# Sheet1.net
KiCad netlist of a schematic drawn in Altium Designer
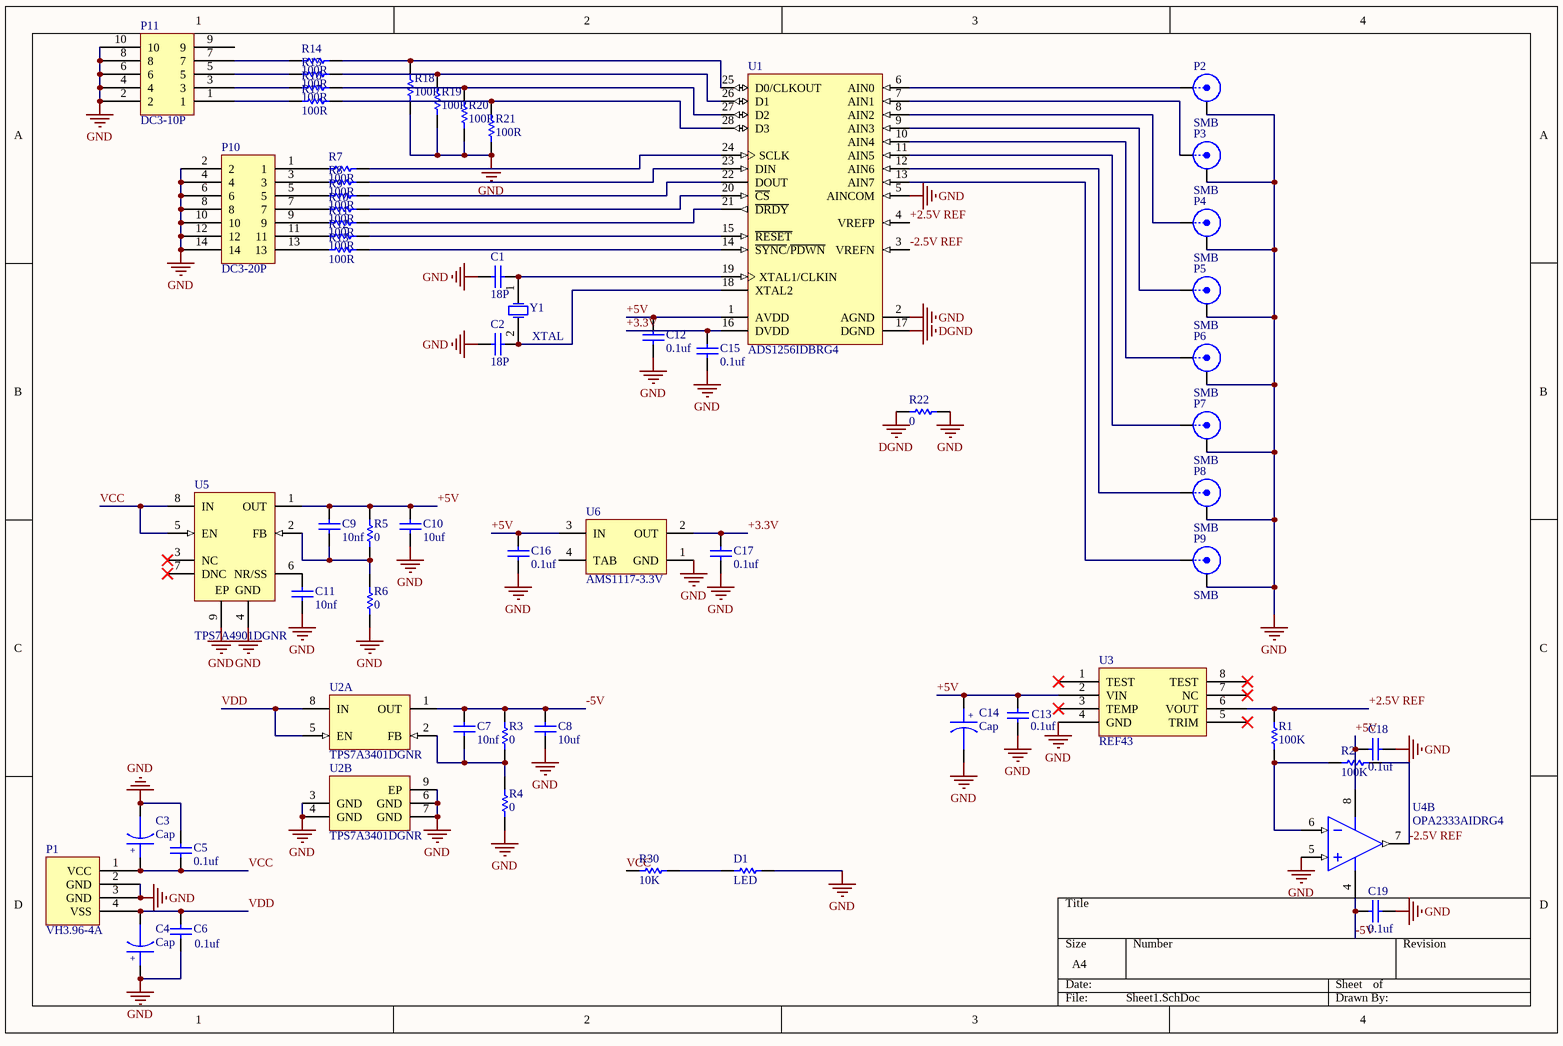
[diagram p0: Sheet1.SchDoc]

(export (version "E")
  (design (tool "Eeschema 10.0.6"))
  (components
    (comp (ref "C1") (value "18P") (footprint "0603C") (libsource (lib "Schlib1") (part "Cap")))
    (comp (ref "C2") (value "18P") (footprint "0603C") (libsource (lib "Schlib1") (part "Cap")))
    (comp (ref "C3")
      (value "Cap")
      (footprint "7343C-TYPE_D")
      (libsource (lib "Schlib1") (part "Tantalium Cap"))
    )
    (comp (ref "C4")
      (value "Cap")
      (footprint "7343C-TYPE_D")
      (libsource (lib "Schlib1") (part "Tantalium Cap"))
    )
    (comp (ref "C5") (value "0.1uf") (footprint "0805") (libsource (lib "Schlib1") (part "Cap")))
    (comp (ref "C6") (value "0.1uf") (footprint "0805") (libsource (lib "Schlib1") (part "Cap")))
    (comp (ref "C7") (value "10nf") (footprint "0805") (libsource (lib "Schlib1") (part "Cap")))
    (comp (ref "C8") (value "10uf") (footprint "0805") (libsource (lib "Schlib1") (part "Cap")))
    (comp (ref "C9") (value "10nf") (footprint "0805") (libsource (lib "Schlib1") (part "Cap")))
    (comp (ref "C10") (value "10uf") (footprint "0805") (libsource (lib "Schlib1") (part "Cap")))
    (comp (ref "C11") (value "10nf") (footprint "0805") (libsource (lib "Schlib1") (part "Cap")))
    (comp (ref "C12") (value "0.1uf") (footprint "0805") (libsource (lib "Schlib1") (part "Cap")))
    (comp (ref "C13") (value "0.1uf") (footprint "0805") (libsource (lib "Schlib1") (part "Cap")))
    (comp (ref "C14")
      (value "Cap")
      (footprint "3216C-TYPE_A")
      (libsource (lib "Schlib1") (part "Tantalium Cap"))
    )
    (comp (ref "C15") (value "0.1uf") (footprint "0805") (libsource (lib "Schlib1") (part "Cap")))
    (comp (ref "C16") (value "0.1uf") (footprint "0805") (libsource (lib "Schlib1") (part "Cap")))
    (comp (ref "C17") (value "0.1uf") (footprint "0805") (libsource (lib "Schlib1") (part "Cap")))
    (comp (ref "C18") (value "0.1uf") (footprint "3216C-TYPE_A") (libsource (lib "Schlib1") (part "Cap")))
    (comp (ref "C19") (value "0.1uf") (footprint "3216C-TYPE_A") (libsource (lib "Schlib1") (part "Cap")))
    (comp (ref "D1") (value "LED") (footprint "0805") (libsource (lib "Schlib1") (part "Res")))
    (comp (ref "P1")
      (value "VH3.96-4A")
      (footprint "VH3.96-4P")
      (libsource (lib "Schlib1") (part "VH3.96-4A"))
    )
    (comp (ref "P2")
      (value "SMB")
      (footprint "SMB_V-RJ45")
      (description "SMB Straight Connector")
      (fields (field (name "PUBLISHER") "Altium Limited"))
      (libsource (lib "Miscellaneous Connectors") (part "SMB"))
    )
    (comp (ref "P3")
      (value "SMB")
      (footprint "SMB_V-RJ45")
      (description "SMB Straight Connector")
      (fields (field (name "PUBLISHER") "Altium Limited"))
      (libsource (lib "Miscellaneous Connectors") (part "SMB"))
    )
    (comp (ref "P4")
      (value "SMB")
      (footprint "SMB_V-RJ45")
      (description "SMB Straight Connector")
      (fields (field (name "PUBLISHER") "Altium Limited"))
      (libsource (lib "Miscellaneous Connectors") (part "SMB"))
    )
    (comp (ref "P5")
      (value "SMB")
      (footprint "SMB_V-RJ45")
      (description "SMB Straight Connector")
      (fields (field (name "PUBLISHER") "Altium Limited"))
      (libsource (lib "Miscellaneous Connectors") (part "SMB"))
    )
    (comp (ref "P6")
      (value "SMB")
      (footprint "SMB_V-RJ45")
      (description "SMB Straight Connector")
      (fields (field (name "PUBLISHER") "Altium Limited"))
      (libsource (lib "Miscellaneous Connectors") (part "SMB"))
    )
    (comp (ref "P7")
      (value "SMB")
      (footprint "SMB_V-RJ45")
      (description "SMB Straight Connector")
      (fields (field (name "PUBLISHER") "Altium Limited"))
      (libsource (lib "Miscellaneous Connectors") (part "SMB"))
    )
    (comp (ref "P8")
      (value "SMB")
      (footprint "SMB_V-RJ45")
      (description "SMB Straight Connector")
      (fields (field (name "PUBLISHER") "Altium Limited"))
      (libsource (lib "Miscellaneous Connectors") (part "SMB"))
    )
    (comp (ref "P9")
      (value "SMB")
      (footprint "SMB_V-RJ45")
      (description "SMB Straight Connector")
      (fields (field (name "PUBLISHER") "Altium Limited"))
      (libsource (lib "Miscellaneous Connectors") (part "SMB"))
    )
    (comp (ref "P10") (value "DC3-20P") (footprint "DC3-14P") (libsource (lib "Schlib1") (part "DC3-20P")))
    (comp (ref "P11") (value "DC3-10P") (footprint "DC3-10P") (libsource (lib "Schlib1") (part "DC3-10P")))
    (comp (ref "R1") (value "100K") (footprint "0805") (libsource (lib "Schlib1") (part "Res")))
    (comp (ref "R2") (value "100K") (footprint "0805") (libsource (lib "Schlib1") (part "Res")))
    (comp (ref "R3") (value "0") (footprint "0805") (libsource (lib "Schlib1") (part "Res")))
    (comp (ref "R4") (value "0") (footprint "0805") (libsource (lib "Schlib1") (part "Res")))
    (comp (ref "R5") (value "0") (footprint "0805") (libsource (lib "Schlib1") (part "Res")))
    (comp (ref "R6") (value "0") (footprint "0805") (libsource (lib "Schlib1") (part "Res")))
    (comp (ref "R7") (value "100R") (footprint "0805") (libsource (lib "Schlib1") (part "Res")))
    (comp (ref "R8") (value "100R") (footprint "0805") (libsource (lib "Schlib1") (part "Res")))
    (comp (ref "R9") (value "100R") (footprint "0805") (libsource (lib "Schlib1") (part "Res")))
    (comp (ref "R10") (value "100R") (footprint "0805") (libsource (lib "Schlib1") (part "Res")))
    (comp (ref "R11") (value "100R") (footprint "0805") (libsource (lib "Schlib1") (part "Res")))
    (comp (ref "R12") (value "100R") (footprint "0805") (libsource (lib "Schlib1") (part "Res")))
    (comp (ref "R13") (value "100R") (footprint "0805") (libsource (lib "Schlib1") (part "Res")))
    (comp (ref "R14") (value "100R") (footprint "0805") (libsource (lib "Schlib1") (part "Res")))
    (comp (ref "R15") (value "100R") (footprint "0805") (libsource (lib "Schlib1") (part "Res")))
    (comp (ref "R16") (value "100R") (footprint "0805") (libsource (lib "Schlib1") (part "Res")))
    (comp (ref "R17") (value "100R") (footprint "0805") (libsource (lib "Schlib1") (part "Res")))
    (comp (ref "R18") (value "100R") (footprint "0805") (libsource (lib "Schlib1") (part "Res")))
    (comp (ref "R19") (value "100R") (footprint "0805") (libsource (lib "Schlib1") (part "Res")))
    (comp (ref "R20") (value "100R") (footprint "0805") (libsource (lib "Schlib1") (part "Res")))
    (comp (ref "R21") (value "100R") (footprint "0805") (libsource (lib "Schlib1") (part "Res")))
    (comp (ref "R22") (value "0") (footprint "0805") (libsource (lib "Schlib1") (part "Res")))
    (comp (ref "R30") (value "10K") (footprint "0805") (libsource (lib "Schlib1") (part "Res")))
    (comp (ref "U1")
      (value "ADS1256IDBRG4")
      (footprint "TI-DB28_N")
      (fields (field (name "MANUFACTURER") "Texas Instruments"))
      (libsource (lib "Schlib1") (part "ADS1256IDBRG4"))
    )
    (comp (ref "U2")
      (value "TPS7A3401DGNR")
      (footprint "TI-DGN8-1760X1425TP_N")
      (fields (field (name "MANUFACTURER") "Texas Instruments"))
      (libsource (lib "Schlib1") (part "TPS7A3401DGNR"))
    )
    (comp (ref "U3") (value "REF43") (footprint "TI-D8_M") (libsource (lib "Schlib1") (part "REF43")))
    (comp (ref "U4")
      (value "OPA2333AIDRG4")
      (footprint "TI-D8_N")
      (fields (field (name "MANUFACTURER") "Texas Instruments"))
      (libsource (lib "Schlib1") (part "OPA2333AIDRG4"))
    )
    (comp (ref "U5")
      (value "TPS7A4901DGNR")
      (footprint "TI-DGN8-1760X1425TP_N")
      (fields (field (name "MANUFACTURER") "Texas Instruments"))
      (libsource (lib "Schlib1") (part "TPS7A4901DGNR"))
    )
    (comp (ref "U6")
      (value "AMS1117-3.3V")
      (footprint "SOT-223")
      (libsource (lib "Schlib1") (part "AMS1117-3.3V"))
    )
    (comp (ref "Y1")
      (value "XTAL")
      (footprint "HC-49S")
      (description "Crystal Oscillator")
      (fields (field (name "PUBLISHER") "Altium Limited"))
      (libsource (lib "Miscellaneous Devices") (part "XTAL"))
    )
  )
  (nets
    (net (code "1") (name "/+2.5V REF") (class "Default")
      (node (ref "R1") (pin "2") (pinfunction "2_2") (pintype "passive"))
      (node (ref "U1") (pin "4") (pinfunction "VREFP_4") (pintype "input"))
      (node (ref "U3") (pin "6") (pinfunction "VOUT_6") (pintype "passive"))
    )
    (net (code "2") (name "/+3.3V") (class "Default")
      (node (ref "C15") (pin "2") (pinfunction "2_2") (pintype "passive"))
      (node (ref "C17") (pin "2") (pinfunction "2_2") (pintype "passive"))
      (node (ref "U1") (pin "16") (pinfunction "DVDD_16") (pintype "power_in"))
      (node (ref "U6") (pin "2") (pinfunction "OUT_2") (pintype "power_in"))
    )
    (net (code "3") (name "/+5V") (class "Default")
      (node (ref "C10") (pin "2") (pinfunction "2_2") (pintype "passive"))
      (node (ref "C12") (pin "2") (pinfunction "2_2") (pintype "passive"))
      (node (ref "C13") (pin "2") (pinfunction "2_2") (pintype "passive"))
      (node (ref "C14") (pin "1") (pinfunction "1_1") (pintype "passive"))
      (node (ref "C16") (pin "2") (pinfunction "2_2") (pintype "passive"))
      (node (ref "C18") (pin "1") (pinfunction "1_1") (pintype "passive"))
      (node (ref "C9") (pin "2") (pinfunction "2_2") (pintype "passive"))
      (node (ref "R5") (pin "2") (pinfunction "2_2") (pintype "passive"))
      (node (ref "U1") (pin "1") (pinfunction "AVDD_1") (pintype "power_in"))
      (node (ref "U3") (pin "2") (pinfunction "VIN_2") (pintype "passive"))
      (node (ref "U4") (pin "8") (pinfunction "V+_8") (pintype "power_in"))
      (node (ref "U5") (pin "1") (pinfunction "OUT_1") (pintype "power_in"))
      (node (ref "U6") (pin "3") (pinfunction "IN_3") (pintype "power_in"))
    )
    (net (code "4") (name "/-2.5V REF") (class "Default")
      (node (ref "R2") (pin "1") (pinfunction "1_1") (pintype "passive"))
      (node (ref "U1") (pin "3") (pinfunction "VREFN_3") (pintype "input"))
      (node (ref "U4") (pin "7") (pinfunction "OUT_B_7") (pintype "output"))
    )
    (net (code "5") (name "/-5V") (class "Default")
      (node (ref "C19") (pin "1") (pinfunction "1_1") (pintype "passive"))
      (node (ref "C7") (pin "2") (pinfunction "2_2") (pintype "passive"))
      (node (ref "C8") (pin "2") (pinfunction "2_2") (pintype "passive"))
      (node (ref "R3") (pin "2") (pinfunction "2_2") (pintype "passive"))
      (node (ref "U2") (pin "1") (pinfunction "OUT_1") (pintype "power_in"))
      (node (ref "U4") (pin "4") (pinfunction "V-_4") (pintype "power_in"))
    )
    (net (code "6") (name "/VCC") (class "Default")
      (node (ref "C3") (pin "1") (pinfunction "1_1") (pintype "passive"))
      (node (ref "C5") (pin "1") (pinfunction "1_1") (pintype "passive"))
      (node (ref "P1") (pin "1") (pinfunction "VCC_1") (pintype "passive"))
      (node (ref "R30") (pin "1") (pinfunction "1_1") (pintype "passive"))
      (node (ref "U5") (pin "5") (pinfunction "EN_5") (pintype "input"))
      (node (ref "U5") (pin "8") (pinfunction "IN_8") (pintype "power_in"))
    )
    (net (code "7") (name "/VDD") (class "Default")
      (node (ref "C4") (pin "2") (pinfunction "2_2") (pintype "passive"))
      (node (ref "C6") (pin "1") (pinfunction "1_1") (pintype "passive"))
      (node (ref "P1") (pin "4") (pinfunction "VSS_4") (pintype "passive"))
      (node (ref "U2") (pin "5") (pinfunction "EN_5") (pintype "input"))
      (node (ref "U2") (pin "8") (pinfunction "IN_8") (pintype "power_in"))
    )
    (net (code "8") (name "DGND") (class "Default")
      (node (ref "R22") (pin "1") (pinfunction "1_1") (pintype "passive"))
      (node (ref "U1") (pin "17") (pinfunction "DGND_17") (pintype "power_in"))
    )
    (net (code "9") (name "GND") (class "Default")
      (node (ref "C1") (pin "1") (pinfunction "1_1") (pintype "passive"))
      (node (ref "C10") (pin "1") (pinfunction "1_1") (pintype "passive"))
      (node (ref "C11") (pin "1") (pinfunction "1_1") (pintype "passive"))
      (node (ref "C12") (pin "1") (pinfunction "1_1") (pintype "passive"))
      (node (ref "C13") (pin "1") (pinfunction "1_1") (pintype "passive"))
      (node (ref "C14") (pin "2") (pinfunction "2_2") (pintype "passive"))
      (node (ref "C15") (pin "1") (pinfunction "1_1") (pintype "passive"))
      (node (ref "C16") (pin "1") (pinfunction "1_1") (pintype "passive"))
      (node (ref "C17") (pin "1") (pinfunction "1_1") (pintype "passive"))
      (node (ref "C18") (pin "2") (pinfunction "2_2") (pintype "passive"))
      (node (ref "C19") (pin "2") (pinfunction "2_2") (pintype "passive"))
      (node (ref "C2") (pin "1") (pinfunction "1_1") (pintype "passive"))
      (node (ref "C3") (pin "2") (pinfunction "2_2") (pintype "passive"))
      (node (ref "C4") (pin "1") (pinfunction "1_1") (pintype "passive"))
      (node (ref "C5") (pin "2") (pinfunction "2_2") (pintype "passive"))
      (node (ref "C6") (pin "2") (pinfunction "2_2") (pintype "passive"))
      (node (ref "C8") (pin "1") (pinfunction "1_1") (pintype "passive"))
      (node (ref "D1") (pin "2") (pinfunction "2_2") (pintype "passive"))
      (node (ref "P1") (pin "2") (pinfunction "GND_2") (pintype "passive"))
      (node (ref "P1") (pin "3") (pinfunction "GND_3") (pintype "passive"))
      (node (ref "P10") (pin "10") (pinfunction "10_10") (pintype "passive"))
      (node (ref "P10") (pin "12") (pinfunction "12_12") (pintype "passive"))
      (node (ref "P10") (pin "14") (pinfunction "14_14") (pintype "passive"))
      (node (ref "P10") (pin "2") (pinfunction "2_2") (pintype "passive"))
      (node (ref "P10") (pin "4") (pinfunction "4_4") (pintype "passive"))
      (node (ref "P10") (pin "6") (pinfunction "6_6") (pintype "passive"))
      (node (ref "P10") (pin "8") (pinfunction "8_8") (pintype "passive"))
      (node (ref "P11") (pin "10") (pinfunction "10_10") (pintype "passive"))
      (node (ref "P11") (pin "2") (pinfunction "2_2") (pintype "passive"))
      (node (ref "P11") (pin "4") (pinfunction "4_4") (pintype "passive"))
      (node (ref "P11") (pin "6") (pinfunction "6_6") (pintype "passive"))
      (node (ref "P11") (pin "8") (pinfunction "8_8") (pintype "passive"))
      (node (ref "P2") (pin "2") (pinfunction "Y_2") (pintype "passive"))
      (node (ref "P3") (pin "2") (pinfunction "Y_2") (pintype "passive"))
      (node (ref "P4") (pin "2") (pinfunction "Y_2") (pintype "passive"))
      (node (ref "P5") (pin "2") (pinfunction "Y_2") (pintype "passive"))
      (node (ref "P6") (pin "2") (pinfunction "Y_2") (pintype "passive"))
      (node (ref "P7") (pin "2") (pinfunction "Y_2") (pintype "passive"))
      (node (ref "P8") (pin "2") (pinfunction "Y_2") (pintype "passive"))
      (node (ref "P9") (pin "2") (pinfunction "Y_2") (pintype "passive"))
      (node (ref "R18") (pin "1") (pinfunction "1_1") (pintype "passive"))
      (node (ref "R19") (pin "1") (pinfunction "1_1") (pintype "passive"))
      (node (ref "R20") (pin "1") (pinfunction "1_1") (pintype "passive"))
      (node (ref "R21") (pin "1") (pinfunction "1_1") (pintype "passive"))
      (node (ref "R22") (pin "2") (pinfunction "2_2") (pintype "passive"))
      (node (ref "R4") (pin "1") (pinfunction "1_1") (pintype "passive"))
      (node (ref "R6") (pin "1") (pinfunction "1_1") (pintype "passive"))
      (node (ref "U1") (pin "2") (pinfunction "AGND_2") (pintype "power_in"))
      (node (ref "U1") (pin "5") (pinfunction "AINCOM_5") (pintype "input"))
      (node (ref "U2") (pin "3") (pinfunction "GND_3") (pintype "power_in"))
      (node (ref "U2") (pin "4") (pinfunction "GND_4") (pintype "power_in"))
      (node (ref "U2") (pin "6") (pinfunction "GND_6") (pintype "power_in"))
      (node (ref "U2") (pin "7") (pinfunction "GND_7") (pintype "power_in"))
      (node (ref "U2") (pin "9") (pinfunction "EP_9") (pintype "power_in"))
      (node (ref "U3") (pin "4") (pinfunction "GND_4") (pintype "passive"))
      (node (ref "U4") (pin "5") (pinfunction "IN_B+_5") (pintype "input"))
      (node (ref "U5") (pin "4") (pinfunction "GND_4") (pintype "power_in"))
      (node (ref "U5") (pin "9") (pinfunction "EP_9") (pintype "power_in"))
      (node (ref "U6") (pin "1") (pinfunction "GND_1") (pintype "power_in"))
    )
    (net (code "10") (name "Net-(D1-Pad1)") (class "Default")
      (node (ref "D1") (pin "1") (pinfunction "1_1") (pintype "passive"))
      (node (ref "R30") (pin "2") (pinfunction "2_2") (pintype "passive"))
    )
    (net (code "11") (name "Net-(P2-X)") (class "Default")
      (node (ref "P2") (pin "1") (pinfunction "X_1") (pintype "passive"))
      (node (ref "U1") (pin "6") (pinfunction "AIN0_6") (pintype "input"))
    )
    (net (code "12") (name "Net-(P3-X)") (class "Default")
      (node (ref "P3") (pin "1") (pinfunction "X_1") (pintype "passive"))
      (node (ref "U1") (pin "7") (pinfunction "AIN1_7") (pintype "input"))
    )
    (net (code "13") (name "Net-(P4-X)") (class "Default")
      (node (ref "P4") (pin "1") (pinfunction "X_1") (pintype "passive"))
      (node (ref "U1") (pin "8") (pinfunction "AIN2_8") (pintype "input"))
    )
    (net (code "14") (name "Net-(P5-X)") (class "Default")
      (node (ref "P5") (pin "1") (pinfunction "X_1") (pintype "passive"))
      (node (ref "U1") (pin "9") (pinfunction "AIN3_9") (pintype "input"))
    )
    (net (code "15") (name "Net-(P6-X)") (class "Default")
      (node (ref "P6") (pin "1") (pinfunction "X_1") (pintype "passive"))
      (node (ref "U1") (pin "10") (pinfunction "AIN4_10") (pintype "input"))
    )
    (net (code "16") (name "Net-(P7-X)") (class "Default")
      (node (ref "P7") (pin "1") (pinfunction "X_1") (pintype "passive"))
      (node (ref "U1") (pin "11") (pinfunction "AIN5_11") (pintype "input"))
    )
    (net (code "17") (name "Net-(P8-X)") (class "Default")
      (node (ref "P8") (pin "1") (pinfunction "X_1") (pintype "passive"))
      (node (ref "U1") (pin "12") (pinfunction "AIN6_12") (pintype "input"))
    )
    (net (code "18") (name "Net-(P9-X)") (class "Default")
      (node (ref "P9") (pin "1") (pinfunction "X_1") (pintype "passive"))
      (node (ref "U1") (pin "13") (pinfunction "AIN7_13") (pintype "input"))
    )
    (net (code "19") (name "Net-(P10-Pad1)") (class "Default")
      (node (ref "P10") (pin "1") (pinfunction "1_1") (pintype "passive"))
      (node (ref "R7") (pin "1") (pinfunction "1_1") (pintype "passive"))
    )
    (net (code "20") (name "Net-(P10-Pad3)") (class "Default")
      (node (ref "P10") (pin "3") (pinfunction "3_3") (pintype "passive"))
      (node (ref "R8") (pin "1") (pinfunction "1_1") (pintype "passive"))
    )
    (net (code "21") (name "Net-(P10-Pad5)") (class "Default")
      (node (ref "P10") (pin "5") (pinfunction "5_5") (pintype "passive"))
      (node (ref "R9") (pin "1") (pinfunction "1_1") (pintype "passive"))
    )
    (net (code "22") (name "Net-(P10-Pad7)") (class "Default")
      (node (ref "P10") (pin "7") (pinfunction "7_7") (pintype "passive"))
      (node (ref "R10") (pin "1") (pinfunction "1_1") (pintype "passive"))
    )
    (net (code "23") (name "Net-(P10-Pad9)") (class "Default")
      (node (ref "P10") (pin "9") (pinfunction "9_9") (pintype "passive"))
      (node (ref "R11") (pin "1") (pinfunction "1_1") (pintype "passive"))
    )
    (net (code "24") (name "Net-(P10-Pad11)") (class "Default")
      (node (ref "P10") (pin "11") (pinfunction "11_11") (pintype "passive"))
      (node (ref "R12") (pin "1") (pinfunction "1_1") (pintype "passive"))
    )
    (net (code "25") (name "Net-(P10-Pad13)") (class "Default")
      (node (ref "P10") (pin "13") (pinfunction "13_13") (pintype "passive"))
      (node (ref "R13") (pin "1") (pinfunction "1_1") (pintype "passive"))
    )
    (net (code "26") (name "Net-(P11-Pad1)") (class "Default")
      (node (ref "P11") (pin "1") (pinfunction "1_1") (pintype "passive"))
      (node (ref "R17") (pin "1") (pinfunction "1_1") (pintype "passive"))
    )
    (net (code "27") (name "Net-(P11-Pad3)") (class "Default")
      (node (ref "P11") (pin "3") (pinfunction "3_3") (pintype "passive"))
      (node (ref "R16") (pin "1") (pinfunction "1_1") (pintype "passive"))
    )
    (net (code "28") (name "Net-(P11-Pad5)") (class "Default")
      (node (ref "P11") (pin "5") (pinfunction "5_5") (pintype "passive"))
      (node (ref "R15") (pin "1") (pinfunction "1_1") (pintype "passive"))
    )
    (net (code "29") (name "Net-(P11-Pad7)") (class "Default")
      (node (ref "P11") (pin "7") (pinfunction "7_7") (pintype "passive"))
      (node (ref "R14") (pin "1") (pinfunction "1_1") (pintype "passive"))
    )
    (net (code "30") (name "Net-(U1-D0{slash}CLKOUT)") (class "Default")
      (node (ref "R14") (pin "2") (pinfunction "2_2") (pintype "passive"))
      (node (ref "R18") (pin "2") (pinfunction "2_2") (pintype "passive"))
      (node (ref "U1") (pin "25") (pinfunction "D0/CLKOUT_25") (pintype "bidirectional"))
    )
    (net (code "31") (name "Net-(U1-D1)") (class "Default")
      (node (ref "R15") (pin "2") (pinfunction "2_2") (pintype "passive"))
      (node (ref "R19") (pin "2") (pinfunction "2_2") (pintype "passive"))
      (node (ref "U1") (pin "26") (pinfunction "D1_26") (pintype "bidirectional"))
    )
    (net (code "32") (name "Net-(U1-D2)") (class "Default")
      (node (ref "R16") (pin "2") (pinfunction "2_2") (pintype "passive"))
      (node (ref "R20") (pin "2") (pinfunction "2_2") (pintype "passive"))
      (node (ref "U1") (pin "27") (pinfunction "D2_27") (pintype "bidirectional"))
    )
    (net (code "33") (name "Net-(U1-D3)") (class "Default")
      (node (ref "R17") (pin "2") (pinfunction "2_2") (pintype "passive"))
      (node (ref "R21") (pin "2") (pinfunction "2_2") (pintype "passive"))
      (node (ref "U1") (pin "28") (pinfunction "D3_28") (pintype "bidirectional"))
    )
    (net (code "34") (name "Net-(U1-DIN)") (class "Default")
      (node (ref "R8") (pin "2") (pinfunction "2_2") (pintype "passive"))
      (node (ref "U1") (pin "23") (pinfunction "DIN_23") (pintype "input"))
    )
    (net (code "35") (name "Net-(U1-DOUT)") (class "Default")
      (node (ref "R9") (pin "2") (pinfunction "2_2") (pintype "passive"))
      (node (ref "U1") (pin "22") (pinfunction "DOUT_22") (pintype "tri_state"))
    )
    (net (code "36") (name "Net-(U1-SCLK)") (class "Default")
      (node (ref "R7") (pin "2") (pinfunction "2_2") (pintype "passive"))
      (node (ref "U1") (pin "24") (pinfunction "SCLK_24") (pintype "input"))
    )
    (net (code "37") (name "Net-(U1-XTAL1{slash}CLKIN)") (class "Default")
      (node (ref "C1") (pin "2") (pinfunction "2_2") (pintype "passive"))
      (node (ref "U1") (pin "19") (pinfunction "XTAL1/CLKIN_19") (pintype "input"))
      (node (ref "Y1") (pin "1") (pinfunction "OSC1_1") (pintype "passive"))
    )
    (net (code "38") (name "Net-(U1-XTAL2)") (class "Default")
      (node (ref "C2") (pin "2") (pinfunction "2_2") (pintype "passive"))
      (node (ref "U1") (pin "18") (pinfunction "XTAL2_18") (pintype "passive"))
      (node (ref "Y1") (pin "2") (pinfunction "OSC2_2") (pintype "passive"))
    )
    (net (code "39") (name "Net-(U1-~{CS})") (class "Default")
      (node (ref "R10") (pin "2") (pinfunction "2_2") (pintype "passive"))
      (node (ref "U1") (pin "20") (pinfunction "~{CS}_20") (pintype "input"))
    )
    (net (code "40") (name "Net-(U1-~{DRDY})") (class "Default")
      (node (ref "R11") (pin "2") (pinfunction "2_2") (pintype "passive"))
      (node (ref "U1") (pin "21") (pinfunction "~{DRDY}_21") (pintype "output"))
    )
    (net (code "41") (name "Net-(U1-~{RESET})") (class "Default")
      (node (ref "R12") (pin "2") (pinfunction "2_2") (pintype "passive"))
      (node (ref "U1") (pin "15") (pinfunction "~{RESET}_15") (pintype "input"))
    )
    (net (code "42") (name "Net-(U1-~{SYNC}{slash}~{PDWN})") (class "Default")
      (node (ref "R13") (pin "2") (pinfunction "2_2") (pintype "passive"))
      (node (ref "U1") (pin "14") (pinfunction "~{SYNC}/~{PDWN}_14") (pintype "input"))
    )
    (net (code "43") (name "Net-(U2A-FB)") (class "Default")
      (node (ref "C7") (pin "1") (pinfunction "1_1") (pintype "passive"))
      (node (ref "R3") (pin "1") (pinfunction "1_1") (pintype "passive"))
      (node (ref "R4") (pin "2") (pinfunction "2_2") (pintype "passive"))
      (node (ref "U2") (pin "2") (pinfunction "FB_2") (pintype "input"))
    )
    (net (code "44") (name "Net-(U4B-IN_B-)") (class "Default")
      (node (ref "R1") (pin "1") (pinfunction "1_1") (pintype "passive"))
      (node (ref "R2") (pin "2") (pinfunction "2_2") (pintype "passive"))
      (node (ref "U4") (pin "6") (pinfunction "IN_B-_6") (pintype "input"))
    )
    (net (code "45") (name "Net-(U5-FB)") (class "Default")
      (node (ref "C9") (pin "1") (pinfunction "1_1") (pintype "passive"))
      (node (ref "R5") (pin "1") (pinfunction "1_1") (pintype "passive"))
      (node (ref "R6") (pin "2") (pinfunction "2_2") (pintype "passive"))
      (node (ref "U5") (pin "2") (pinfunction "FB_2") (pintype "input"))
    )
    (net (code "46") (name "Net-(U5-NR{slash}SS)") (class "Default")
      (node (ref "C11") (pin "2") (pinfunction "2_2") (pintype "passive"))
      (node (ref "U5") (pin "6") (pinfunction "NR/SS_6") (pintype "passive"))
    )
    (net (code "47") (name "unconnected-(P11-Pad9)") (class "Default")
      (node (ref "P11") (pin "9") (pinfunction "9_9") (pintype "passive"))
    )
    (net (code "48") (name "unconnected-(U3-NC-Pad7)") (class "Default")
      (node (ref "U3") (pin "7") (pinfunction "NC_7") (pintype "passive+no_connect"))
    )
    (net (code "49") (name "unconnected-(U3-TEMP-Pad3)") (class "Default")
      (node (ref "U3") (pin "3") (pinfunction "TEMP_3") (pintype "passive+no_connect"))
    )
    (net (code "50") (name "unconnected-(U3-TEST-Pad1)") (class "Default")
      (node (ref "U3") (pin "1") (pinfunction "TEST_1") (pintype "passive+no_connect"))
    )
    (net (code "51") (name "unconnected-(U3-TEST-Pad8)") (class "Default")
      (node (ref "U3") (pin "8") (pinfunction "TEST_8") (pintype "passive+no_connect"))
    )
    (net (code "52") (name "unconnected-(U3-TRIM-Pad5)") (class "Default")
      (node (ref "U3") (pin "5") (pinfunction "TRIM_5") (pintype "passive+no_connect"))
    )
    (net (code "53") (name "unconnected-(U5-DNC-Pad7)") (class "Default")
      (node (ref "U5") (pin "7") (pinfunction "DNC_7") (pintype "passive+no_connect"))
    )
    (net (code "54") (name "unconnected-(U5-NC-Pad3)") (class "Default")
      (node (ref "U5") (pin "3") (pinfunction "NC_3") (pintype "passive+no_connect"))
    )
    (net (code "55") (name "unconnected-(U6-TAB-Pad4)") (class "Default")
      (node (ref "U6") (pin "4") (pinfunction "TAB_4") (pintype "power_in"))
    )
  )
)
